# Rtc.net
KiCad netlist of a schematic drawn in Altium Designer
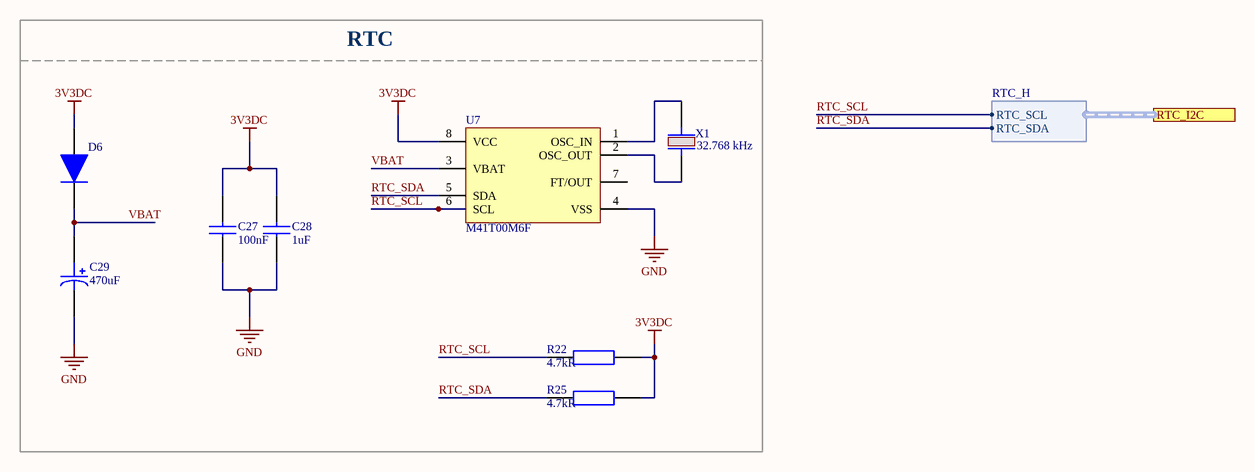
[diagram p0: Rtc.SchDoc]

(export (version "E")
  (design (tool "Eeschema 10.0.6"))
  (components
    (comp (ref "C27")
      (value "CL21B104KBCNNNC")
      (footprint "CAP_0805")
      (description "CAP CER 100nF %10 0805")
      (fields
        (field (name "MANUFACTURER") "Samsung")
        (field (name "TOLERANCE") "10%")
        (field (name "CAPACITANCE") "100nF")
        (field (name "DESIGNED BY") "BERK")
      )
      (libsource (lib "GuvenlikSistemi_Library") (part "CAP CER 100nF 0805"))
    )
    (comp (ref "C28")
      (value "CL21B105KBFNNNE")
      (footprint "CAP_0805")
      (description "CAP CER 1uF %10 0805")
      (fields
        (field (name "MANUFACTURER") "Samsung")
        (field (name "TOLERANCE") "10%")
        (field (name "CAPACITANCE") "1uF")
        (field (name "DESIGNED BY") "BERK")
      )
      (libsource (lib "GuvenlikSistemi_Library") (part "CAP CER 1uF 0805"))
    )
    (comp (ref "C29")
      (value "ESH477M050AH4AA")
      (footprint "CAP_RADIAL_D10_P5")
      (description "CAP ALU ELEC 470uF 50V RADIAL")
      (fields
        (field (name "MANUFACTURER") "KEMET")
        (field (name "TOLERANCE") "20%")
        (field (name "CAPACITANCE") "470uF")
        (field (name "DESIGNED BY") "BERK")
      )
      (libsource (lib "GuvenlikSistemi_Library") (part "CAP ALU ELEC 470uF 50V"))
    )
    (comp (ref "D6")
      (value "1N4148WS")
      (footprint "SOD323F")
      (description "Diode, Single, 75 V, 150 mA, 1 V, 4 ns")
      (fields
        (field (name "MANUFACTURER") "ON Semiconductor / Fairchild")
        (field (name "DESIGNED BY") "BERK")
      )
      (libsource (lib "GuvenlikSistemi_Library") (part "1N4148WS"))
    )
    (comp (ref "R22")
      (value "RC0603JR-074K7L")
      (footprint "RES_0603")
      (description "RES 4K7 %5 OHM 0603 SMD")
      (fields
        (field (name "MANUFACTURER") "Yageo")
        (field (name "TOLERANCE") "5%")
        (field (name "RESISTANCE") "4.7kR")
        (field (name "DESIGNED BY") "BERK")
      )
      (libsource (lib "GuvenlikSistemi_Library") (part "RES 4K7 OHM 0603"))
    )
    (comp (ref "R25")
      (value "RC0603JR-074K7L")
      (footprint "RES_0603")
      (description "RES 4K7 %5 OHM 0603 SMD")
      (fields
        (field (name "MANUFACTURER") "Yageo")
        (field (name "TOLERANCE") "5%")
        (field (name "RESISTANCE") "4.7kR")
        (field (name "DESIGNED BY") "BERK")
      )
      (libsource (lib "GuvenlikSistemi_Library") (part "RES 4K7 OHM 0603"))
    )
    (comp (ref "U7")
      (value "M41T00M6F")
      (footprint "SOIC8")
      (description "IC RTC CLK/CALENDAR I2C 8-SOIC")
      (fields (field (name "MANUFACTURER") "STMicroelectronics") (field (name "DESIGNED BY") "BERK"))
      (libsource (lib "GuvenlikSistemi_Library") (part "M41T00M6F"))
    )
    (comp (ref "X1")
      (value "ABS05-32.768KHZ-T")
      (footprint "ABS05")
      (description "Crystal, 32.768 kHz, SMD, 1.6mm x 1mm, 12.5 pF, 20 ppm, ABS05 Series")
      (fields
        (field (name "MANUFACTURER") "Abracon")
        (field (name "TOLERANCE") "20ppm")
        (field (name "OPERATING FREQUENCY") "32.768 kHz")
        (field (name "DESIGNED BY") "BERK")
      )
      (libsource (lib "GuvenlikSistemi_Library") (part "CRYSTAL 32768kHZ"))
    )
  )
  (nets
    (net (code "2") (name "/RTC_SCL") (class "Default")
      (node (ref "R22") (pin "1") (pinfunction "1_1") (pintype "passive"))
      (node (ref "U7") (pin "6") (pinfunction "SCL_6") (pintype "passive"))
    )
    (net (code "3") (name "/RTC_SDA") (class "Default")
      (node (ref "R25") (pin "1") (pinfunction "1_1") (pintype "passive"))
      (node (ref "U7") (pin "5") (pinfunction "SDA_5") (pintype "passive"))
    )
    (net (code "4") (name "/VBAT") (class "Default")
      (node (ref "C29") (pin "1") (pinfunction "1_1") (pintype "passive"))
      (node (ref "D6") (pin "1") (pinfunction "1_1") (pintype "power_in"))
      (node (ref "U7") (pin "3") (pinfunction "VBAT_3") (pintype "passive"))
    )
    (net (code "6") (name "3V3DC") (class "Default")
      (node (ref "C27") (pin "2") (pinfunction "2_2") (pintype "passive"))
      (node (ref "C28") (pin "2") (pinfunction "2_2") (pintype "passive"))
      (node (ref "D6") (pin "2") (pinfunction "2_2") (pintype "power_in"))
      (node (ref "R22") (pin "2") (pinfunction "2_2") (pintype "passive"))
      (node (ref "R25") (pin "2") (pinfunction "2_2") (pintype "passive"))
      (node (ref "U7") (pin "8") (pinfunction "VCC_8") (pintype "passive"))
    )
    (net (code "7") (name "GND") (class "Default")
      (node (ref "C27") (pin "1") (pinfunction "1_1") (pintype "passive"))
      (node (ref "C28") (pin "1") (pinfunction "1_1") (pintype "passive"))
      (node (ref "C29") (pin "2") (pinfunction "2_2") (pintype "passive"))
      (node (ref "U7") (pin "4") (pinfunction "VSS_4") (pintype "passive"))
    )
    (net (code "8") (name "Net-(U7-OSC_IN)") (class "Default")
      (node (ref "U7") (pin "1") (pinfunction "OSC_IN_1") (pintype "passive"))
      (node (ref "X1") (pin "2") (pinfunction "2_2") (pintype "passive"))
    )
    (net (code "9") (name "Net-(U7-OSC_OUT)") (class "Default")
      (node (ref "U7") (pin "2") (pinfunction "OSC_OUT_2") (pintype "passive"))
      (node (ref "X1") (pin "1") (pinfunction "1_1") (pintype "passive"))
    )
    (net (code "10") (name "unconnected-(U7-FT{slash}OUT-Pad7)") (class "Default")
      (node (ref "U7") (pin "7") (pinfunction "FT/OUT_7") (pintype "passive"))
    )
  )
)
